# MercurialSDR_FTDI.net
KiCad netlist of a schematic drawn in Altium Designer
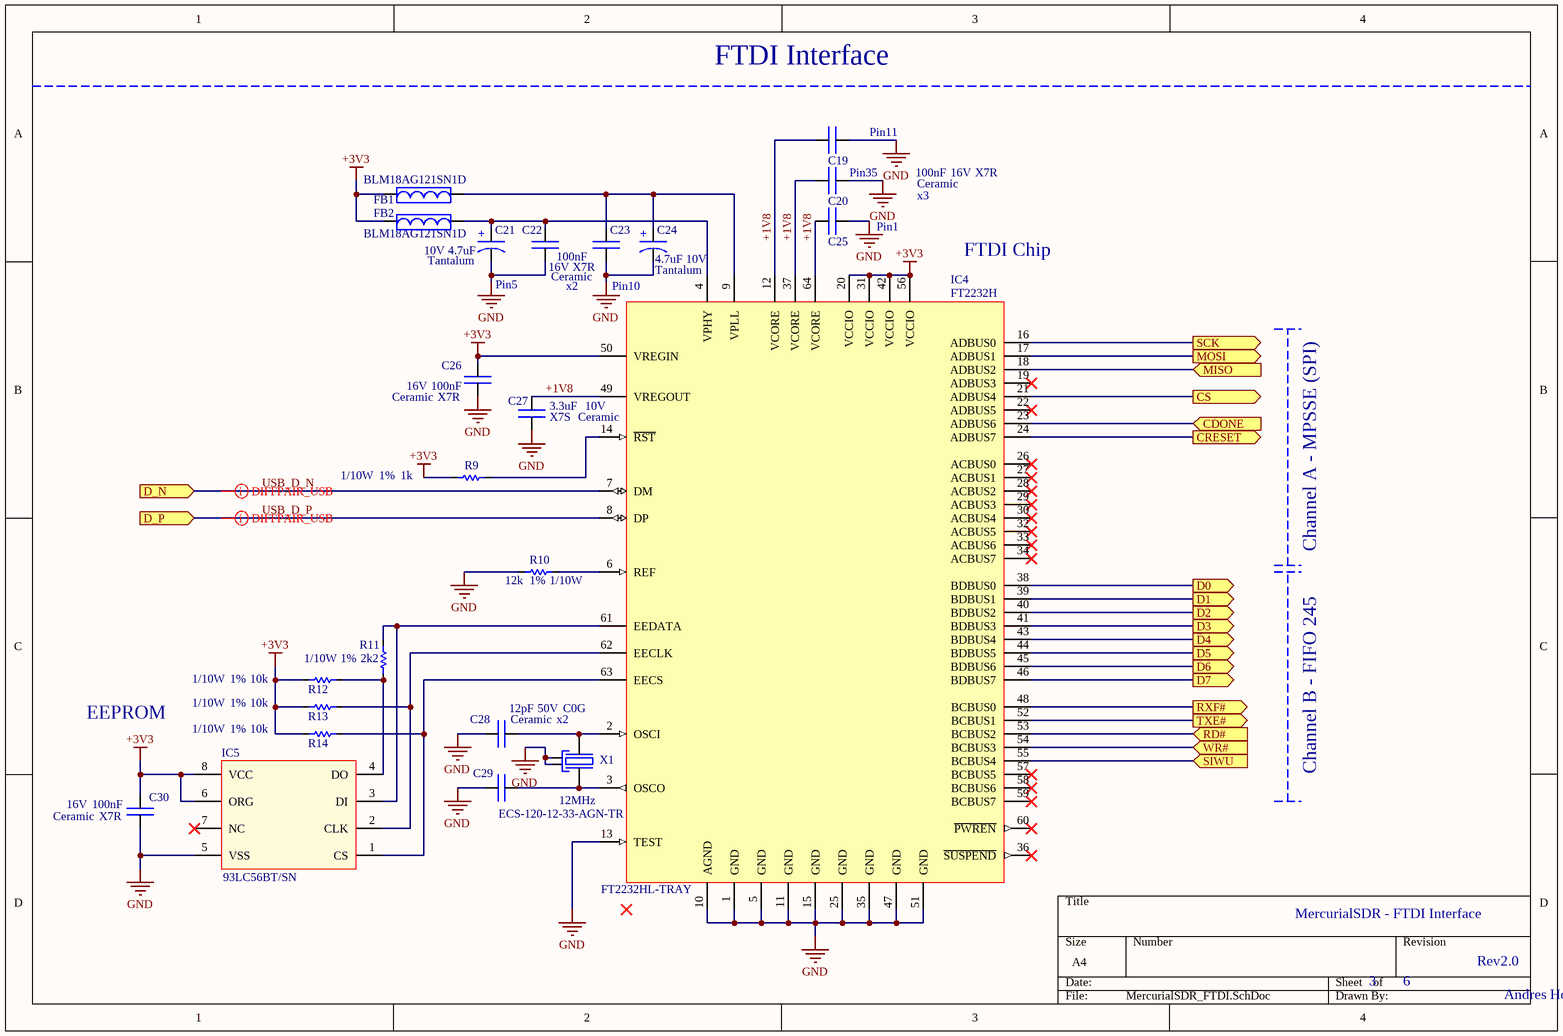
[diagram p0: MercurialSDR_FTDI.SchDoc]

(export (version "E")
  (design (tool "Eeschema 10.0.6"))
  (components
    (comp (ref "C19")
      (value "100nF")
      (footprint "CAP_0603")
      (description "Capacitor no polarizado")
      (fields
        (field (name "TEMP COEF") "X7R")
        (field (name "PART NUMBER") "CL10B104KO8NNNC")
        (field (name "VR") "16V")
        (field (name "MATERIAL") "Ceramic")
        (field (name "Comment") "Capacitor")
      )
      (libsource (lib "MercurialSDR") (part "Cap"))
    )
    (comp (ref "C20")
      (value "Capacitor")
      (footprint "CAP_0603")
      (description "Capacitor no polarizado")
      (fields (field (name "PART NUMBER") "CL10B104KO8NNNC"))
      (libsource (lib "MercurialSDR") (part "Cap"))
    )
    (comp (ref "C21")
      (value "4.7uF")
      (footprint "CAP_TANT_1206")
      (description "Capacitor polarizado")
      (fields
        (field (name "PART NUMBER") "TAJA475K010RNJ")
        (field (name "VR") "10V")
        (field (name "MATERIAL") "Tantalum")
        (field (name "Comment") "Capacitor Polarizado")
      )
      (libsource (lib "MercurialSDR") (part "Cap Pol"))
    )
    (comp (ref "C22")
      (value "100nF")
      (footprint "CAP_0603")
      (description "Capacitor no polarizado")
      (fields
        (field (name "TEMP COEF") "X7R")
        (field (name "PART NUMBER") "CL10B104KO8NNNC")
        (field (name "VR") "16V")
        (field (name "MATERIAL") "Ceramic")
        (field (name "Comment") "Capacitor")
      )
      (libsource (lib "MercurialSDR") (part "Cap"))
    )
    (comp (ref "C23")
      (value "Capacitor")
      (footprint "CAP_0603")
      (description "Capacitor no polarizado")
      (fields (field (name "PART NUMBER") "CL10B104KO8NNNC"))
      (libsource (lib "MercurialSDR") (part "Cap"))
    )
    (comp (ref "C24")
      (value "4.7uF")
      (footprint "CAP_TANT_1206")
      (description "Capacitor polarizado")
      (fields
        (field (name "PART NUMBER") "TAJA475K010RNJ")
        (field (name "VR") "10V")
        (field (name "MATERIAL") "Tantalum")
        (field (name "Comment") "Capacitor Polarizado")
      )
      (libsource (lib "MercurialSDR") (part "Cap Pol"))
    )
    (comp (ref "C25")
      (value "Capacitor")
      (footprint "CAP_0603")
      (description "Capacitor no polarizado")
      (fields (field (name "PART NUMBER") "CL10B104KO8NNNC"))
      (libsource (lib "MercurialSDR") (part "Cap"))
    )
    (comp (ref "C26")
      (value "100nF")
      (footprint "CAP_0603")
      (description "Capacitor no polarizado")
      (fields
        (field (name "TEMP COEF") "X7R")
        (field (name "PART NUMBER") "CL10B104KO8NNNC")
        (field (name "VR") "16V")
        (field (name "MATERIAL") "Ceramic")
        (field (name "Comment") "Capacitor")
      )
      (libsource (lib "MercurialSDR") (part "Cap"))
    )
    (comp (ref "C27")
      (value "3.3uF")
      (footprint "CAP_0603")
      (description "Capacitor no polarizado")
      (fields
        (field (name "TEMP COEF") "X7S")
        (field (name "PART NUMBER") "C1608X7S1A335K080AC")
        (field (name "VR") "10V")
        (field (name "MATERIAL") "Ceramic")
        (field (name "Comment") "Capacitor")
      )
      (libsource (lib "MercurialSDR") (part "Cap"))
    )
    (comp (ref "C28")
      (value "12pF")
      (footprint "CAP_0603")
      (description "Capacitor no polarizado")
      (fields
        (field (name "TEMP COEF") "C0G")
        (field (name "PART NUMBER") "CL10C120JB8NNNC")
        (field (name "VR") "50V")
        (field (name "MATERIAL") "Ceramic")
        (field (name "Comment") "Capacitor")
      )
      (libsource (lib "MercurialSDR") (part "Cap"))
    )
    (comp (ref "C29")
      (value "Capacitor")
      (footprint "CAP_0603")
      (description "Capacitor no polarizado")
      (fields (field (name "PART NUMBER") "CL10C120JB8NNNC"))
      (libsource (lib "MercurialSDR") (part "Cap"))
    )
    (comp (ref "C30")
      (value "100nF")
      (footprint "CAP_0603")
      (description "Capacitor no polarizado")
      (fields
        (field (name "TEMP COEF") "X7R")
        (field (name "PART NUMBER") "CL10B104KO8NNNC")
        (field (name "VR") "16V")
        (field (name "MATERIAL") "Ceramic")
        (field (name "Comment") "Capacitor")
      )
      (libsource (lib "MercurialSDR") (part "Cap"))
    )
    (comp (ref "FB1")
      (value "Ferrite Bead")
      (footprint "FERRITE_BEAD_0603")
      (fields (field (name "PART NUMBER") "BLM18AG121SN1D"))
      (libsource (lib "MercurialSDR") (part "Ferrite Bead"))
    )
    (comp (ref "FB2")
      (value "Ferrite Bead")
      (footprint "FERRITE_BEAD_0603")
      (fields (field (name "PART NUMBER") "BLM18AG121SN1D"))
      (libsource (lib "MercurialSDR") (part "Ferrite Bead"))
    )
    (comp (ref "IC4")
      (value "FT2232H")
      (footprint "LQFP_64")
      (description "USB bridge")
      (fields (field (name "PART NUMBER") "FT2232HL-TRAY"))
      (libsource (lib "MercurialSDR") (part "FT2232H"))
    )
    (comp (ref "IC5")
      (value "93LC56BT")
      (footprint "SOIC-8")
      (description "EEPROM SPI 2kb (128x16)")
      (fields (field (name "PART NUMBER") "93LC56BT/SN"))
      (libsource (lib "MercurialSDR") (part "93LC56BT/SN"))
    )
    (comp (ref "R9")
      (value "1k")
      (footprint "RES_0603")
      (description "Resistor")
      (fields
        (field (name "POWER") "1/10W")
        (field (name "PART NUMBER") "CR0603-FX-1001ELF")
        (field (name "TOLERANCE") "1%")
        (field (name "Comment") "Resistor SMD")
      )
      (libsource (lib "MercurialSDR") (part "Res"))
    )
    (comp (ref "R10")
      (value "12k")
      (footprint "RES_0603")
      (description "Resistor")
      (fields
        (field (name "POWER") "1/10W")
        (field (name "PART NUMBER") "CR0603-FX-1202ELF")
        (field (name "TOLERANCE") "1%")
        (field (name "Comment") "Resistor SMD")
      )
      (libsource (lib "MercurialSDR") (part "Res"))
    )
    (comp (ref "R11")
      (value "2k2")
      (footprint "RES_0603")
      (description "Resistor")
      (fields
        (field (name "POWER") "1/10W")
        (field (name "PART NUMBER") "AC0603FR-072K2L")
        (field (name "TOLERANCE") "1%")
        (field (name "Comment") "Resistor SMD")
      )
      (libsource (lib "MercurialSDR") (part "Res"))
    )
    (comp (ref "R12")
      (value "10k")
      (footprint "RES_0603")
      (description "Resistor")
      (fields
        (field (name "POWER") "1/10W")
        (field (name "PART NUMBER") "CR0603-FX-1002EAS")
        (field (name "TOLERANCE") "1%")
        (field (name "Comment") "Resistor SMD")
      )
      (libsource (lib "MercurialSDR") (part "Res"))
    )
    (comp (ref "R13")
      (value "10k")
      (footprint "RES_0603")
      (description "Resistor")
      (fields
        (field (name "POWER") "1/10W")
        (field (name "PART NUMBER") "CR0603-FX-1002EAS")
        (field (name "TOLERANCE") "1%")
        (field (name "Comment") "Resistor SMD")
      )
      (libsource (lib "MercurialSDR") (part "Res"))
    )
    (comp (ref "R14")
      (value "10k")
      (footprint "RES_0603")
      (description "Resistor")
      (fields
        (field (name "POWER") "1/10W")
        (field (name "PART NUMBER") "CR0603-FX-1002EAS")
        (field (name "TOLERANCE") "1%")
        (field (name "Comment") "Resistor SMD")
      )
      (libsource (lib "MercurialSDR") (part "Res"))
    )
    (comp (ref "X1")
      (value "XTAL_4term")
      (footprint "XTAL_3.2x2.5")
      (description "Oscilador a Cristal")
      (fields (field (name "PART NUMBER") "ECS-120-12-33-AGN-TR") (field (name "FRQUENCY") "12MHz"))
      (libsource (lib "MercurialSDR") (part "XTAL_4term"))
    )
  )
  (nets
    (net (code "1") (name "+3V3") (class "Default")
      (node (ref "C26") (pin "1") (pinfunction "1_1") (pintype "passive"))
      (node (ref "C30") (pin "1") (pinfunction "1_1") (pintype "passive"))
      (node (ref "FB1") (pin "1") (pinfunction "1_1") (pintype "passive"))
      (node (ref "FB2") (pin "1") (pinfunction "1_1") (pintype "passive"))
      (node (ref "IC4") (pin "20") (pinfunction "VCCIO_20") (pintype "power_in"))
      (node (ref "IC4") (pin "31") (pinfunction "VCCIO_31") (pintype "power_in"))
      (node (ref "IC4") (pin "42") (pinfunction "VCCIO_42") (pintype "power_in"))
      (node (ref "IC4") (pin "50") (pinfunction "VREGIN_50") (pintype "power_in"))
      (node (ref "IC4") (pin "56") (pinfunction "VCCIO_56") (pintype "power_in"))
      (node (ref "IC5") (pin "6") (pinfunction "ORG_6") (pintype "passive"))
      (node (ref "IC5") (pin "8") (pinfunction "VCC_8") (pintype "passive"))
      (node (ref "R12") (pin "2") (pinfunction "2_2") (pintype "passive"))
      (node (ref "R13") (pin "1") (pinfunction "1_1") (pintype "passive"))
      (node (ref "R14") (pin "1") (pinfunction "1_1") (pintype "passive"))
      (node (ref "R9") (pin "2") (pinfunction "2_2") (pintype "passive"))
    )
    (net (code "2") (name "/+1V8") (class "Default")
      (node (ref "C19") (pin "1") (pinfunction "1_1") (pintype "passive"))
      (node (ref "C20") (pin "1") (pinfunction "1_1") (pintype "passive"))
      (node (ref "C25") (pin "1") (pinfunction "1_1") (pintype "passive"))
      (node (ref "C27") (pin "1") (pinfunction "1_1") (pintype "passive"))
      (node (ref "IC4") (pin "12") (pinfunction "VCORE_12") (pintype "power_in"))
      (node (ref "IC4") (pin "37") (pinfunction "VCORE_37") (pintype "power_in"))
      (node (ref "IC4") (pin "49") (pinfunction "VREGOUT_49") (pintype "power_in"))
      (node (ref "IC4") (pin "64") (pinfunction "VCORE_64") (pintype "power_in"))
    )
    (net (code "3") (name "/CDONE") (class "Default")
      (node (ref "IC4") (pin "23") (pinfunction "ADBUS6_23") (pintype "passive"))
    )
    (net (code "4") (name "/CRESET") (class "Default")
      (node (ref "IC4") (pin "24") (pinfunction "ADBUS7_24") (pintype "passive"))
    )
    (net (code "5") (name "/CS") (class "Default")
      (node (ref "IC4") (pin "21") (pinfunction "ADBUS4_21") (pintype "passive"))
    )
    (net (code "6") (name "/D0") (class "Default")
      (node (ref "IC4") (pin "38") (pinfunction "BDBUS0_38") (pintype "passive"))
    )
    (net (code "7") (name "/D1") (class "Default")
      (node (ref "IC4") (pin "39") (pinfunction "BDBUS1_39") (pintype "passive"))
    )
    (net (code "8") (name "/D2") (class "Default")
      (node (ref "IC4") (pin "40") (pinfunction "BDBUS2_40") (pintype "passive"))
    )
    (net (code "9") (name "/D3") (class "Default")
      (node (ref "IC4") (pin "41") (pinfunction "BDBUS3_41") (pintype "passive"))
    )
    (net (code "10") (name "/D4") (class "Default")
      (node (ref "IC4") (pin "43") (pinfunction "BDBUS4_43") (pintype "passive"))
    )
    (net (code "11") (name "/D5") (class "Default")
      (node (ref "IC4") (pin "44") (pinfunction "BDBUS5_44") (pintype "passive"))
    )
    (net (code "12") (name "/D6") (class "Default")
      (node (ref "IC4") (pin "45") (pinfunction "BDBUS6_45") (pintype "passive"))
    )
    (net (code "13") (name "/D7") (class "Default")
      (node (ref "IC4") (pin "46") (pinfunction "BDBUS7_46") (pintype "passive"))
    )
    (net (code "14") (name "/MISO") (class "Default")
      (node (ref "IC4") (pin "18") (pinfunction "ADBUS2_18") (pintype "passive"))
    )
    (net (code "15") (name "/MOSI") (class "Default")
      (node (ref "IC4") (pin "17") (pinfunction "ADBUS1_17") (pintype "passive"))
    )
    (net (code "16") (name "/RD#") (class "Default")
      (node (ref "IC4") (pin "53") (pinfunction "BCBUS2_53") (pintype "passive"))
    )
    (net (code "17") (name "/RXF#") (class "Default")
      (node (ref "IC4") (pin "48") (pinfunction "BCBUS0_48") (pintype "passive"))
    )
    (net (code "18") (name "/SCK") (class "Default")
      (node (ref "IC4") (pin "16") (pinfunction "ADBUS0_16") (pintype "passive"))
    )
    (net (code "19") (name "/SIWU") (class "Default")
      (node (ref "IC4") (pin "55") (pinfunction "BCBUS4_55") (pintype "passive"))
    )
    (net (code "20") (name "/TXE#") (class "Default")
      (node (ref "IC4") (pin "52") (pinfunction "BCBUS1_52") (pintype "passive"))
    )
    (net (code "21") (name "/USB_D_N") (class "Default")
      (node (ref "IC4") (pin "7") (pinfunction "DM_7") (pintype "bidirectional"))
    )
    (net (code "22") (name "/USB_D_P") (class "Default")
      (node (ref "IC4") (pin "8") (pinfunction "DP_8") (pintype "bidirectional"))
    )
    (net (code "23") (name "/WR#") (class "Default")
      (node (ref "IC4") (pin "54") (pinfunction "BCBUS3_54") (pintype "passive"))
    )
    (net (code "24") (name "GND") (class "Default")
      (node (ref "C19") (pin "2") (pinfunction "2_2") (pintype "passive"))
      (node (ref "C20") (pin "2") (pinfunction "2_2") (pintype "passive"))
      (node (ref "C21") (pin "2") (pinfunction "2_2") (pintype "passive"))
      (node (ref "C22") (pin "2") (pinfunction "2_2") (pintype "passive"))
      (node (ref "C23") (pin "2") (pinfunction "2_2") (pintype "passive"))
      (node (ref "C24") (pin "2") (pinfunction "2_2") (pintype "passive"))
      (node (ref "C25") (pin "2") (pinfunction "2_2") (pintype "passive"))
      (node (ref "C26") (pin "2") (pinfunction "2_2") (pintype "passive"))
      (node (ref "C27") (pin "2") (pinfunction "2_2") (pintype "passive"))
      (node (ref "C28") (pin "2") (pinfunction "2_2") (pintype "passive"))
      (node (ref "C29") (pin "1") (pinfunction "1_1") (pintype "passive"))
      (node (ref "C30") (pin "2") (pinfunction "2_2") (pintype "passive"))
      (node (ref "IC4") (pin "1") (pinfunction "GND_1") (pintype "power_in"))
      (node (ref "IC4") (pin "10") (pinfunction "AGND_10") (pintype "power_in"))
      (node (ref "IC4") (pin "11") (pinfunction "GND_11") (pintype "power_in"))
      (node (ref "IC4") (pin "13") (pinfunction "TEST_13") (pintype "input"))
      (node (ref "IC4") (pin "15") (pinfunction "GND_15") (pintype "power_in"))
      (node (ref "IC4") (pin "25") (pinfunction "GND_25") (pintype "power_in"))
      (node (ref "IC4") (pin "35") (pinfunction "GND_35") (pintype "power_in"))
      (node (ref "IC4") (pin "47") (pinfunction "GND_47") (pintype "power_in"))
      (node (ref "IC4") (pin "5") (pinfunction "GND_5") (pintype "power_in"))
      (node (ref "IC4") (pin "51") (pinfunction "GND_51") (pintype "power_in"))
      (node (ref "IC5") (pin "5") (pinfunction "VSS_5") (pintype "passive"))
      (node (ref "R10") (pin "2") (pinfunction "2_2") (pintype "passive"))
      (node (ref "X1") (pin "2") (pinfunction "2_2") (pintype "passive"))
      (node (ref "X1") (pin "4") (pinfunction "4_4") (pintype "passive"))
    )
    (net (code "25") (name "Net-(IC4-EECLK)") (class "Default")
      (node (ref "IC4") (pin "62") (pinfunction "EECLK_62") (pintype "passive"))
      (node (ref "IC5") (pin "2") (pinfunction "CLK_2") (pintype "passive"))
      (node (ref "R13") (pin "2") (pinfunction "2_2") (pintype "passive"))
    )
    (net (code "26") (name "Net-(IC4-EECS)") (class "Default")
      (node (ref "IC4") (pin "63") (pinfunction "EECS_63") (pintype "passive"))
      (node (ref "IC5") (pin "1") (pinfunction "CS_1") (pintype "passive"))
      (node (ref "R14") (pin "2") (pinfunction "2_2") (pintype "passive"))
    )
    (net (code "27") (name "Net-(IC4-EEDATA)") (class "Default")
      (node (ref "IC4") (pin "61") (pinfunction "EEDATA_61") (pintype "passive"))
      (node (ref "IC5") (pin "3") (pinfunction "DI_3") (pintype "passive"))
      (node (ref "R11") (pin "2") (pinfunction "2_2") (pintype "passive"))
    )
    (net (code "28") (name "Net-(IC4-OSCI)") (class "Default")
      (node (ref "C28") (pin "1") (pinfunction "1_1") (pintype "passive"))
      (node (ref "IC4") (pin "2") (pinfunction "OSCI_2") (pintype "input"))
      (node (ref "X1") (pin "1") (pinfunction "1_1") (pintype "passive"))
    )
    (net (code "29") (name "Net-(IC4-OSCO)") (class "Default")
      (node (ref "C29") (pin "2") (pinfunction "2_2") (pintype "passive"))
      (node (ref "IC4") (pin "3") (pinfunction "OSCO_3") (pintype "output"))
      (node (ref "X1") (pin "3") (pinfunction "3_3") (pintype "passive"))
    )
    (net (code "30") (name "Net-(IC4-REF)") (class "Default")
      (node (ref "IC4") (pin "6") (pinfunction "REF_6") (pintype "input"))
      (node (ref "R10") (pin "1") (pinfunction "1_1") (pintype "passive"))
    )
    (net (code "31") (name "Net-(IC4-VPHY)") (class "Default")
      (node (ref "C21") (pin "1") (pinfunction "1_1") (pintype "passive"))
      (node (ref "C22") (pin "1") (pinfunction "1_1") (pintype "passive"))
      (node (ref "FB2") (pin "2") (pinfunction "2_2") (pintype "passive"))
      (node (ref "IC4") (pin "4") (pinfunction "VPHY_4") (pintype "power_in"))
    )
    (net (code "32") (name "Net-(IC4-VPLL)") (class "Default")
      (node (ref "C23") (pin "1") (pinfunction "1_1") (pintype "passive"))
      (node (ref "C24") (pin "1") (pinfunction "1_1") (pintype "passive"))
      (node (ref "FB1") (pin "2") (pinfunction "2_2") (pintype "passive"))
      (node (ref "IC4") (pin "9") (pinfunction "VPLL_9") (pintype "power_in"))
    )
    (net (code "33") (name "Net-(IC4-~{RST})") (class "Default")
      (node (ref "IC4") (pin "14") (pinfunction "~{RST}_14") (pintype "input"))
      (node (ref "R9") (pin "1") (pinfunction "1_1") (pintype "passive"))
    )
    (net (code "34") (name "Net-(IC5-DO)") (class "Default")
      (node (ref "IC5") (pin "4") (pinfunction "DO_4") (pintype "passive"))
      (node (ref "R11") (pin "1") (pinfunction "1_1") (pintype "passive"))
      (node (ref "R12") (pin "1") (pinfunction "1_1") (pintype "passive"))
    )
    (net (code "35") (name "unconnected-(IC4-ACBUS0-Pad26)") (class "Default")
      (node (ref "IC4") (pin "26") (pinfunction "ACBUS0_26") (pintype "passive+no_connect"))
    )
    (net (code "36") (name "unconnected-(IC4-ACBUS1-Pad27)") (class "Default")
      (node (ref "IC4") (pin "27") (pinfunction "ACBUS1_27") (pintype "passive+no_connect"))
    )
    (net (code "37") (name "unconnected-(IC4-ACBUS2-Pad28)") (class "Default")
      (node (ref "IC4") (pin "28") (pinfunction "ACBUS2_28") (pintype "passive+no_connect"))
    )
    (net (code "38") (name "unconnected-(IC4-ACBUS3-Pad29)") (class "Default")
      (node (ref "IC4") (pin "29") (pinfunction "ACBUS3_29") (pintype "passive+no_connect"))
    )
    (net (code "39") (name "unconnected-(IC4-ACBUS4-Pad30)") (class "Default")
      (node (ref "IC4") (pin "30") (pinfunction "ACBUS4_30") (pintype "passive+no_connect"))
    )
    (net (code "40") (name "unconnected-(IC4-ACBUS5-Pad32)") (class "Default")
      (node (ref "IC4") (pin "32") (pinfunction "ACBUS5_32") (pintype "passive+no_connect"))
    )
    (net (code "41") (name "unconnected-(IC4-ACBUS6-Pad33)") (class "Default")
      (node (ref "IC4") (pin "33") (pinfunction "ACBUS6_33") (pintype "passive+no_connect"))
    )
    (net (code "42") (name "unconnected-(IC4-ACBUS7-Pad34)") (class "Default")
      (node (ref "IC4") (pin "34") (pinfunction "ACBUS7_34") (pintype "passive+no_connect"))
    )
    (net (code "43") (name "unconnected-(IC4-ADBUS3-Pad19)") (class "Default")
      (node (ref "IC4") (pin "19") (pinfunction "ADBUS3_19") (pintype "passive+no_connect"))
    )
    (net (code "44") (name "unconnected-(IC4-ADBUS5-Pad22)") (class "Default")
      (node (ref "IC4") (pin "22") (pinfunction "ADBUS5_22") (pintype "passive+no_connect"))
    )
    (net (code "45") (name "unconnected-(IC4-BCBUS5-Pad57)") (class "Default")
      (node (ref "IC4") (pin "57") (pinfunction "BCBUS5_57") (pintype "passive+no_connect"))
    )
    (net (code "46") (name "unconnected-(IC4-BCBUS6-Pad58)") (class "Default")
      (node (ref "IC4") (pin "58") (pinfunction "BCBUS6_58") (pintype "passive+no_connect"))
    )
    (net (code "47") (name "unconnected-(IC4-BCBUS7-Pad59)") (class "Default")
      (node (ref "IC4") (pin "59") (pinfunction "BCBUS7_59") (pintype "passive+no_connect"))
    )
    (net (code "48") (name "unconnected-(IC4-~{PWREN}-Pad60)") (class "Default")
      (node (ref "IC4") (pin "60") (pinfunction "~{PWREN}_60") (pintype "output+no_connect"))
    )
    (net (code "49") (name "unconnected-(IC4-~{SUSPEND}-Pad36)") (class "Default")
      (node (ref "IC4") (pin "36") (pinfunction "~{SUSPEND}_36") (pintype "output+no_connect"))
    )
    (net (code "50") (name "unconnected-(IC5-NC-Pad7)") (class "Default")
      (node (ref "IC5") (pin "7") (pinfunction "NC_7") (pintype "passive+no_connect"))
    )
  )
)
